# M16_EX.net
KiCad netlist of a schematic drawn in Altium Designer
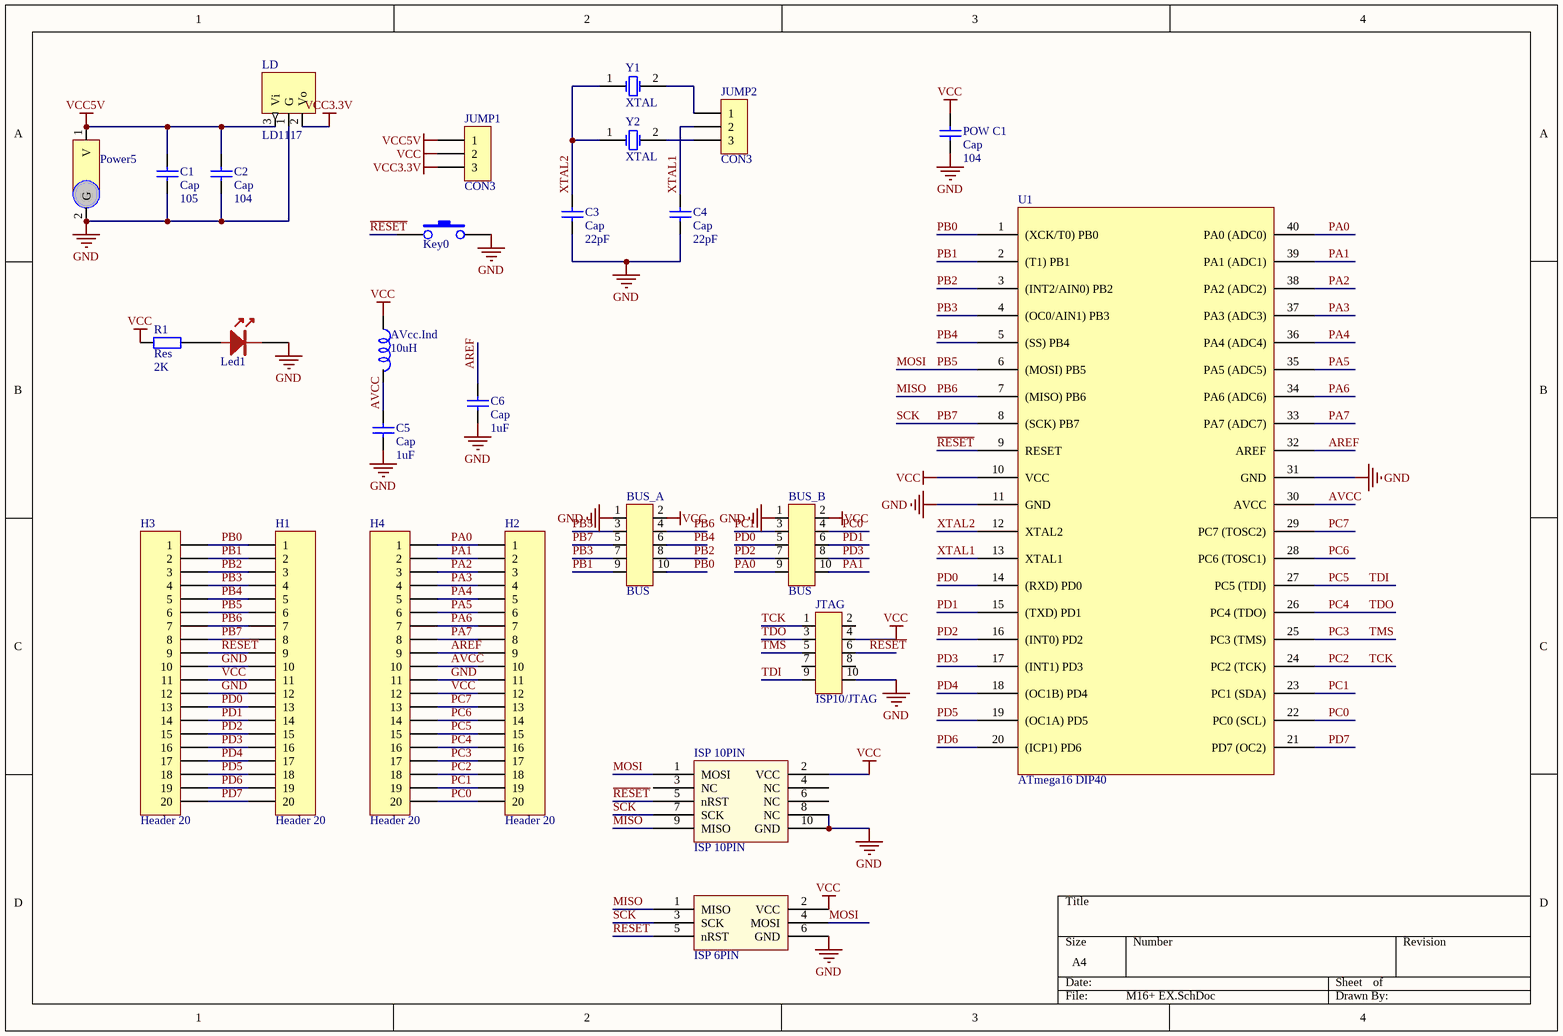
[diagram p0: M16+ EX.SchDoc]

(export (version "E")
  (design (tool "Eeschema 10.0.6"))
  (components
    (comp (ref "AVcc.Ind") (value "10uH") (footprint "RES") (libsource (lib "zz") (part "IND")))
    (comp (ref "BUS_A")
      (value "BUS")
      (footprint "ISP_10")
      (description "ISP_10")
      (libsource (lib "zz") (part "ISP_10"))
    )
    (comp (ref "BUS_B")
      (value "BUS")
      (footprint "ISP_10")
      (description "ISP_10")
      (libsource (lib "zz") (part "ISP_10"))
    )
    (comp (ref "C1")
      (value "Cap")
      (footprint "0805")
      (description "Capacitor")
      (fields (field (name "ALTIUM_VALUE") "105") (field (name "PUBLISHER") "Altium Limited"))
      (libsource (lib "Miscellaneous Devices") (part "Cap"))
    )
    (comp (ref "C2")
      (value "Cap")
      (footprint "0805")
      (description "Capacitor")
      (fields (field (name "ALTIUM_VALUE") "104") (field (name "PUBLISHER") "Altium Limited"))
      (libsource (lib "Miscellaneous Devices") (part "Cap"))
    )
    (comp (ref "C3")
      (value "Cap")
      (footprint "0603")
      (description "Capacitor")
      (fields (field (name "ALTIUM_VALUE") "22pF") (field (name "PUBLISHER") "Altium Limited"))
      (libsource (lib "Miscellaneous Devices") (part "Cap"))
    )
    (comp (ref "C4")
      (value "Cap")
      (footprint "0603")
      (description "Capacitor")
      (fields (field (name "ALTIUM_VALUE") "22pF") (field (name "PUBLISHER") "Altium Limited"))
      (libsource (lib "Miscellaneous Devices") (part "Cap"))
    )
    (comp (ref "C5")
      (value "Cap")
      (footprint "0805")
      (description "Capacitor")
      (fields (field (name "ALTIUM_VALUE") "1uF") (field (name "PUBLISHER") "Altium Limited"))
      (libsource (lib "Miscellaneous Devices") (part "Cap"))
    )
    (comp (ref "C6")
      (value "Cap")
      (footprint "0805")
      (description "Capacitor")
      (fields (field (name "ALTIUM_VALUE") "1uF") (field (name "PUBLISHER") "Altium Limited"))
      (libsource (lib "Miscellaneous Devices") (part "Cap"))
    )
    (comp (ref "H1")
      (value "Header 20")
      (footprint "SIP20")
      (description "Header, 20-Pin")
      (fields (field (name "PUBLISHER") "Altium Limited"))
      (libsource (lib "zz") (part "Header 20"))
    )
    (comp (ref "H2")
      (value "Header 20")
      (footprint "SIP20")
      (description "Header, 20-Pin")
      (fields (field (name "PUBLISHER") "Altium Limited"))
      (libsource (lib "zz") (part "Header 20"))
    )
    (comp (ref "H3")
      (value "Header 20")
      (footprint "SIP20")
      (description "Header, 20-Pin")
      (fields (field (name "PUBLISHER") "Altium Limited"))
      (libsource (lib "") (part "Header 20_1"))
    )
    (comp (ref "H4")
      (value "Header 20")
      (footprint "SIP20")
      (description "Header, 20-Pin")
      (fields (field (name "PUBLISHER") "Altium Limited"))
      (libsource (lib "") (part "Header 20_1"))
    )
    (comp (ref "ISP 6PIN") (value "ISP 6PIN") (footprint "ISP_6") (libsource (lib "zz") (part "ISP 6PIN")))
    (comp (ref "ISP 10PIN")
      (value "ISP 10PIN")
      (footprint "ISP_10")
      (libsource (lib "zz") (part "ISP 10PIN"))
    )
    (comp (ref "JTAG")
      (value "ISP10/JTAG")
      (footprint "ISP_10")
      (description "ISP_10")
      (libsource (lib "zz") (part "ISP_10"))
    )
    (comp (ref "JUMP1")
      (value "CON3")
      (footprint "SIP3")
      (description "Connector")
      (libsource (lib "zz") (part "CON3"))
    )
    (comp (ref "JUMP2")
      (value "CON3")
      (footprint "SIP3")
      (description "Connector")
      (libsource (lib "zz") (part "CON3"))
    )
    (comp (ref "Key0") (value "PB2") (footprint "KEY") (libsource (lib "zz") (part "KEY")))
    (comp (ref "LD") (value "LD1117") (footprint "LD1117-3.3") (libsource (lib "zz") (part "LD1117")))
    (comp (ref "Led1") (value "Led1") (footprint "0805_LED") (libsource (lib "zz") (part "LED")))
    (comp (ref "POW C1")
      (value "Cap")
      (footprint "0805")
      (description "Capacitor")
      (fields (field (name "ALTIUM_VALUE") "104") (field (name "PUBLISHER") "Altium Limited"))
      (libsource (lib "Miscellaneous Devices") (part "Cap"))
    )
    (comp (ref "Power5")
      (value "5V")
      (footprint "PWR_5V")
      (description "Power5")
      (libsource (lib "zz") (part "Power5"))
    )
    (comp (ref "R1")
      (value "Res")
      (footprint "0603")
      (description "Resistor")
      (fields (field (name "ALTIUM_VALUE") "2K") (field (name "PUBLISHER") "Altium Limited"))
      (libsource (lib "Miscellaneous Devices") (part "Res2"))
    )
    (comp (ref "U1")
      (value "ATmega16 DIP40")
      (footprint "DIP40 3M")
      (libsource (lib "zz") (part "ATmega16 DIP40"))
    )
    (comp (ref "Y1")
      (value "XTAL")
      (footprint "CRYSTAL")
      (description "Crystal Oscillator")
      (fields (field (name "PUBLISHER") "Altium Limited"))
      (libsource (lib "zz") (part "XTAL"))
    )
    (comp (ref "Y2")
      (value "XTAL")
      (footprint "CRYSTAL2")
      (description "Crystal Oscillator")
      (fields (field (name "PUBLISHER") "Altium Limited"))
      (libsource (lib "zz") (part "XTAL"))
    )
  )
  (nets
    (net (code "1") (name "/AREF") (class "Default")
      (node (ref "C6") (pin "2") (pinfunction "2_2") (pintype "passive"))
      (node (ref "H2") (pin "9") (pinfunction "9_9") (pintype "passive"))
      (node (ref "H4") (pin "9") (pinfunction "9_9") (pintype "passive"))
      (node (ref "U1") (pin "32") (pinfunction "AREF_32") (pintype "passive"))
    )
    (net (code "2") (name "/AVCC") (class "Default")
      (node (ref "AVcc.Ind") (pin "2") (pinfunction "1_2") (pintype "passive"))
      (node (ref "C5") (pin "2") (pinfunction "2_2") (pintype "passive"))
      (node (ref "H2") (pin "10") (pinfunction "10_10") (pintype "passive"))
      (node (ref "H4") (pin "10") (pinfunction "10_10") (pintype "passive"))
      (node (ref "U1") (pin "30") (pinfunction "AVCC_30") (pintype "passive"))
    )
    (net (code "3") (name "/MISO") (class "Default")
      (node (ref "BUS_A") (pin "4") (pintype "passive"))
      (node (ref "H1") (pin "7") (pinfunction "7_7") (pintype "passive"))
      (node (ref "H3") (pin "7") (pinfunction "7_7") (pintype "passive"))
      (node (ref "ISP 10PIN") (pin "9") (pinfunction "MISO_9") (pintype "passive"))
      (node (ref "ISP 6PIN") (pin "1") (pinfunction "MISO_1") (pintype "passive"))
      (node (ref "U1") (pin "7") (pinfunction "(MISO)_PB6_7") (pintype "passive"))
    )
    (net (code "4") (name "/MOSI") (class "Default")
      (node (ref "BUS_A") (pin "3") (pintype "passive"))
      (node (ref "H1") (pin "6") (pinfunction "6_6") (pintype "passive"))
      (node (ref "H3") (pin "6") (pinfunction "6_6") (pintype "passive"))
      (node (ref "ISP 10PIN") (pin "1") (pinfunction "MOSI_1") (pintype "passive"))
      (node (ref "ISP 6PIN") (pin "4") (pinfunction "MOSI_4") (pintype "passive"))
      (node (ref "U1") (pin "6") (pinfunction "(MOSI)_PB5_6") (pintype "passive"))
    )
    (net (code "5") (name "/PA0") (class "Default")
      (node (ref "BUS_B") (pin "9") (pintype "passive"))
      (node (ref "H2") (pin "1") (pinfunction "1_1") (pintype "passive"))
      (node (ref "H4") (pin "1") (pinfunction "1_1") (pintype "passive"))
      (node (ref "U1") (pin "40") (pinfunction "PA0_(ADC0)_40") (pintype "passive"))
    )
    (net (code "6") (name "/PA1") (class "Default")
      (node (ref "BUS_B") (pin "10") (pintype "passive"))
      (node (ref "H2") (pin "2") (pinfunction "2_2") (pintype "passive"))
      (node (ref "H4") (pin "2") (pinfunction "2_2") (pintype "passive"))
      (node (ref "U1") (pin "39") (pinfunction "PA1_(ADC1)_39") (pintype "passive"))
    )
    (net (code "7") (name "/PA2") (class "Default")
      (node (ref "H2") (pin "3") (pinfunction "3_3") (pintype "passive"))
      (node (ref "H4") (pin "3") (pinfunction "3_3") (pintype "passive"))
      (node (ref "U1") (pin "38") (pinfunction "PA2_(ADC2)_38") (pintype "passive"))
    )
    (net (code "8") (name "/PA3") (class "Default")
      (node (ref "H2") (pin "4") (pinfunction "4_4") (pintype "passive"))
      (node (ref "H4") (pin "4") (pinfunction "4_4") (pintype "passive"))
      (node (ref "U1") (pin "37") (pinfunction "PA3_(ADC3)_37") (pintype "passive"))
    )
    (net (code "9") (name "/PA4") (class "Default")
      (node (ref "H2") (pin "5") (pinfunction "5_5") (pintype "passive"))
      (node (ref "H4") (pin "5") (pinfunction "5_5") (pintype "passive"))
      (node (ref "U1") (pin "36") (pinfunction "PA4_(ADC4)_36") (pintype "passive"))
    )
    (net (code "10") (name "/PA5") (class "Default")
      (node (ref "H2") (pin "6") (pinfunction "6_6") (pintype "passive"))
      (node (ref "H4") (pin "6") (pinfunction "6_6") (pintype "passive"))
      (node (ref "U1") (pin "35") (pinfunction "PA5_(ADC5)_35") (pintype "passive"))
    )
    (net (code "11") (name "/PA6") (class "Default")
      (node (ref "H2") (pin "7") (pinfunction "7_7") (pintype "passive"))
      (node (ref "H4") (pin "7") (pinfunction "7_7") (pintype "passive"))
      (node (ref "U1") (pin "34") (pinfunction "PA6_(ADC6)_34") (pintype "passive"))
    )
    (net (code "12") (name "/PA7") (class "Default")
      (node (ref "H2") (pin "8") (pinfunction "8_8") (pintype "passive"))
      (node (ref "H4") (pin "8") (pinfunction "8_8") (pintype "passive"))
      (node (ref "U1") (pin "33") (pinfunction "PA7_(ADC7)_33") (pintype "passive"))
    )
    (net (code "13") (name "/PB0") (class "Default")
      (node (ref "BUS_A") (pin "10") (pintype "passive"))
      (node (ref "H1") (pin "1") (pinfunction "1_1") (pintype "passive"))
      (node (ref "H3") (pin "1") (pinfunction "1_1") (pintype "passive"))
      (node (ref "U1") (pin "1") (pinfunction "(XCK/T0)_PB0_1") (pintype "passive"))
    )
    (net (code "14") (name "/PB1") (class "Default")
      (node (ref "BUS_A") (pin "9") (pintype "passive"))
      (node (ref "H1") (pin "2") (pinfunction "2_2") (pintype "passive"))
      (node (ref "H3") (pin "2") (pinfunction "2_2") (pintype "passive"))
      (node (ref "U1") (pin "2") (pinfunction "(T1)_PB1_2") (pintype "passive"))
    )
    (net (code "15") (name "/PB2") (class "Default")
      (node (ref "BUS_A") (pin "8") (pintype "passive"))
      (node (ref "H1") (pin "3") (pinfunction "3_3") (pintype "passive"))
      (node (ref "H3") (pin "3") (pinfunction "3_3") (pintype "passive"))
      (node (ref "U1") (pin "3") (pinfunction "(INT2/AIN0)_PB2_3") (pintype "passive"))
    )
    (net (code "16") (name "/PB3") (class "Default")
      (node (ref "BUS_A") (pin "7") (pintype "passive"))
      (node (ref "H1") (pin "4") (pinfunction "4_4") (pintype "passive"))
      (node (ref "H3") (pin "4") (pinfunction "4_4") (pintype "passive"))
      (node (ref "U1") (pin "4") (pinfunction "(OC0/AIN1)_PB3_4") (pintype "passive"))
    )
    (net (code "17") (name "/PB4") (class "Default")
      (node (ref "BUS_A") (pin "6") (pintype "passive"))
      (node (ref "H1") (pin "5") (pinfunction "5_5") (pintype "passive"))
      (node (ref "H3") (pin "5") (pinfunction "5_5") (pintype "passive"))
      (node (ref "U1") (pin "5") (pinfunction "(SS)_PB4_5") (pintype "passive"))
    )
    (net (code "18") (name "/PB7") (class "Default")
      (node (ref "BUS_A") (pin "5") (pintype "passive"))
      (node (ref "H1") (pin "8") (pinfunction "8_8") (pintype "passive"))
      (node (ref "H3") (pin "8") (pinfunction "8_8") (pintype "passive"))
      (node (ref "ISP 10PIN") (pin "7") (pinfunction "SCK_7") (pintype "passive"))
      (node (ref "ISP 6PIN") (pin "3") (pinfunction "SCK_3") (pintype "passive"))
      (node (ref "U1") (pin "8") (pinfunction "(SCK)_PB7_8") (pintype "passive"))
    )
    (net (code "19") (name "/PC0") (class "Default")
      (node (ref "BUS_B") (pin "4") (pintype "passive"))
      (node (ref "H2") (pin "20") (pinfunction "20_20") (pintype "passive"))
      (node (ref "H4") (pin "20") (pinfunction "20_20") (pintype "passive"))
      (node (ref "U1") (pin "22") (pinfunction "PC0_(SCL)_22") (pintype "passive"))
    )
    (net (code "20") (name "/PC1") (class "Default")
      (node (ref "BUS_B") (pin "3") (pintype "passive"))
      (node (ref "H2") (pin "19") (pinfunction "19_19") (pintype "passive"))
      (node (ref "H4") (pin "19") (pinfunction "19_19") (pintype "passive"))
      (node (ref "U1") (pin "23") (pinfunction "PC1_(SDA)_23") (pintype "passive"))
    )
    (net (code "21") (name "/PC2") (class "Default")
      (node (ref "H2") (pin "18") (pinfunction "18_18") (pintype "passive"))
      (node (ref "H4") (pin "18") (pinfunction "18_18") (pintype "passive"))
      (node (ref "JTAG") (pin "1") (pintype "passive"))
      (node (ref "U1") (pin "24") (pinfunction "PC2_(TCK)_24") (pintype "passive"))
    )
    (net (code "22") (name "/PC3") (class "Default")
      (node (ref "H2") (pin "17") (pinfunction "17_17") (pintype "passive"))
      (node (ref "H4") (pin "17") (pinfunction "17_17") (pintype "passive"))
      (node (ref "JTAG") (pin "5") (pintype "passive"))
      (node (ref "U1") (pin "25") (pinfunction "PC3_(TMS)_25") (pintype "passive"))
    )
    (net (code "23") (name "/PC4") (class "Default")
      (node (ref "H2") (pin "16") (pinfunction "16_16") (pintype "passive"))
      (node (ref "H4") (pin "16") (pinfunction "16_16") (pintype "passive"))
      (node (ref "JTAG") (pin "3") (pintype "passive"))
      (node (ref "U1") (pin "26") (pinfunction "PC4_(TDO)_26") (pintype "passive"))
    )
    (net (code "24") (name "/PC5") (class "Default")
      (node (ref "H2") (pin "15") (pinfunction "15_15") (pintype "passive"))
      (node (ref "H4") (pin "15") (pinfunction "15_15") (pintype "passive"))
      (node (ref "JTAG") (pin "9") (pintype "passive"))
      (node (ref "U1") (pin "27") (pinfunction "PC5_(TDI)_27") (pintype "passive"))
    )
    (net (code "25") (name "/PC6") (class "Default")
      (node (ref "H2") (pin "14") (pinfunction "14_14") (pintype "passive"))
      (node (ref "H4") (pin "14") (pinfunction "14_14") (pintype "passive"))
      (node (ref "U1") (pin "28") (pinfunction "PC6_(TOSC1)_28") (pintype "passive"))
    )
    (net (code "26") (name "/PC7") (class "Default")
      (node (ref "H2") (pin "13") (pinfunction "13_13") (pintype "passive"))
      (node (ref "H4") (pin "13") (pinfunction "13_13") (pintype "passive"))
      (node (ref "U1") (pin "29") (pinfunction "PC7_(TOSC2)_29") (pintype "passive"))
    )
    (net (code "27") (name "/PD0") (class "Default")
      (node (ref "BUS_B") (pin "5") (pintype "passive"))
      (node (ref "H1") (pin "13") (pinfunction "13_13") (pintype "passive"))
      (node (ref "H3") (pin "13") (pinfunction "13_13") (pintype "passive"))
      (node (ref "U1") (pin "14") (pinfunction "(RXD)_PD0_14") (pintype "passive"))
    )
    (net (code "28") (name "/PD1") (class "Default")
      (node (ref "BUS_B") (pin "6") (pintype "passive"))
      (node (ref "H1") (pin "14") (pinfunction "14_14") (pintype "passive"))
      (node (ref "H3") (pin "14") (pinfunction "14_14") (pintype "passive"))
      (node (ref "U1") (pin "15") (pinfunction "(TXD)_PD1_15") (pintype "passive"))
    )
    (net (code "29") (name "/PD2") (class "Default")
      (node (ref "BUS_B") (pin "7") (pintype "passive"))
      (node (ref "H1") (pin "15") (pinfunction "15_15") (pintype "passive"))
      (node (ref "H3") (pin "15") (pinfunction "15_15") (pintype "passive"))
      (node (ref "U1") (pin "16") (pinfunction "(INT0)_PD2_16") (pintype "passive"))
    )
    (net (code "30") (name "/PD3") (class "Default")
      (node (ref "BUS_B") (pin "8") (pintype "passive"))
      (node (ref "H1") (pin "16") (pinfunction "16_16") (pintype "passive"))
      (node (ref "H3") (pin "16") (pinfunction "16_16") (pintype "passive"))
      (node (ref "U1") (pin "17") (pinfunction "(INT1)_PD3_17") (pintype "passive"))
    )
    (net (code "31") (name "/PD4") (class "Default")
      (node (ref "H1") (pin "17") (pinfunction "17_17") (pintype "passive"))
      (node (ref "H3") (pin "17") (pinfunction "17_17") (pintype "passive"))
      (node (ref "U1") (pin "18") (pinfunction "(OC1B)_PD4_18") (pintype "passive"))
    )
    (net (code "32") (name "/PD5") (class "Default")
      (node (ref "H1") (pin "18") (pinfunction "18_18") (pintype "passive"))
      (node (ref "H3") (pin "18") (pinfunction "18_18") (pintype "passive"))
      (node (ref "U1") (pin "19") (pinfunction "(OC1A)_PD5_19") (pintype "passive"))
    )
    (net (code "33") (name "/PD6") (class "Default")
      (node (ref "H1") (pin "19") (pinfunction "19_19") (pintype "passive"))
      (node (ref "H3") (pin "19") (pinfunction "19_19") (pintype "passive"))
      (node (ref "U1") (pin "20") (pinfunction "(ICP1)_PD6_20") (pintype "passive"))
    )
    (net (code "34") (name "/PD7") (class "Default")
      (node (ref "H1") (pin "20") (pinfunction "20_20") (pintype "passive"))
      (node (ref "H3") (pin "20") (pinfunction "20_20") (pintype "passive"))
      (node (ref "U1") (pin "21") (pinfunction "PD7_(OC2)_21") (pintype "passive"))
    )
    (net (code "35") (name "/XTAL1") (class "Default")
      (node (ref "C4") (pin "2") (pinfunction "2_2") (pintype "passive"))
      (node (ref "JUMP2") (pin "2") (pinfunction "2_2") (pintype "passive"))
      (node (ref "U1") (pin "13") (pinfunction "XTAL1_13") (pintype "passive"))
    )
    (net (code "36") (name "/XTAL2") (class "Default")
      (node (ref "C3") (pin "2") (pinfunction "2_2") (pintype "passive"))
      (node (ref "U1") (pin "12") (pinfunction "XTAL2_12") (pintype "passive"))
      (node (ref "Y1") (pin "1") (pinfunction "OSC1_1") (pintype "passive"))
      (node (ref "Y2") (pin "1") (pinfunction "OSC1_1") (pintype "passive"))
    )
    (net (code "37") (name "/~{RESET}") (class "Default")
      (node (ref "H1") (pin "9") (pinfunction "9_9") (pintype "passive"))
      (node (ref "H3") (pin "9") (pinfunction "9_9") (pintype "passive"))
      (node (ref "ISP 10PIN") (pin "5") (pinfunction "nRST_5") (pintype "passive"))
      (node (ref "ISP 6PIN") (pin "5") (pinfunction "nRST_5") (pintype "passive"))
      (node (ref "JTAG") (pin "6") (pintype "passive"))
      (node (ref "Key0") (pin "1") (pinfunction "1_1") (pintype "passive"))
      (node (ref "U1") (pin "9") (pinfunction "RESET_9") (pintype "passive"))
    )
    (net (code "38") (name "GND") (class "Default")
      (node (ref "BUS_A") (pin "1") (pintype "passive"))
      (node (ref "BUS_B") (pin "1") (pintype "passive"))
      (node (ref "C1") (pin "1") (pinfunction "1_1") (pintype "passive"))
      (node (ref "C2") (pin "1") (pinfunction "1_1") (pintype "passive"))
      (node (ref "C3") (pin "1") (pinfunction "1_1") (pintype "passive"))
      (node (ref "C4") (pin "1") (pinfunction "1_1") (pintype "passive"))
      (node (ref "C5") (pin "1") (pinfunction "1_1") (pintype "passive"))
      (node (ref "C6") (pin "1") (pinfunction "1_1") (pintype "passive"))
      (node (ref "H1") (pin "10") (pinfunction "10_10") (pintype "passive"))
      (node (ref "H1") (pin "12") (pinfunction "12_12") (pintype "passive"))
      (node (ref "H2") (pin "11") (pinfunction "11_11") (pintype "passive"))
      (node (ref "H3") (pin "10") (pinfunction "10_10") (pintype "passive"))
      (node (ref "H3") (pin "12") (pinfunction "12_12") (pintype "passive"))
      (node (ref "H4") (pin "11") (pinfunction "11_11") (pintype "passive"))
      (node (ref "ISP 10PIN") (pin "10") (pinfunction "GND_10") (pintype "passive"))
      (node (ref "ISP 10PIN") (pin "8") (pinfunction "NC_8") (pintype "passive"))
      (node (ref "ISP 6PIN") (pin "6") (pinfunction "GND_6") (pintype "passive"))
      (node (ref "JTAG") (pin "10") (pintype "passive"))
      (node (ref "Key0") (pin "2") (pinfunction "2_2") (pintype "passive"))
      (node (ref "LD") (pin "1") (pinfunction "G_1") (pintype "passive"))
      (node (ref "Led1") (pin "2") (pinfunction "2_2") (pintype "passive"))
      (node (ref "POW C1") (pin "1") (pinfunction "1_1") (pintype "passive"))
      (node (ref "Power5") (pin "2") (pinfunction "G_2") (pintype "passive"))
      (node (ref "U1") (pin "11") (pinfunction "GND_11") (pintype "passive"))
      (node (ref "U1") (pin "31") (pinfunction "GND_31") (pintype "passive"))
    )
    (net (code "39") (name "Net-(Led1-Pad1)") (class "Default")
      (node (ref "Led1") (pin "1") (pinfunction "1_1") (pintype "passive"))
      (node (ref "R1") (pin "1") (pinfunction "1_1") (pintype "passive"))
    )
    (net (code "40") (name "Net-(Y1-OSC2)") (class "Default")
      (node (ref "JUMP2") (pin "1") (pinfunction "1_1") (pintype "passive"))
      (node (ref "Y1") (pin "2") (pinfunction "OSC2_2") (pintype "passive"))
    )
    (net (code "41") (name "Net-(Y2-OSC2)") (class "Default")
      (node (ref "JUMP2") (pin "3") (pinfunction "3_3") (pintype "passive"))
      (node (ref "Y2") (pin "2") (pinfunction "OSC2_2") (pintype "passive"))
    )
    (net (code "42") (name "VCC") (class "Default")
      (node (ref "AVcc.Ind") (pin "1") (pinfunction "0_1") (pintype "passive"))
      (node (ref "BUS_A") (pin "2") (pintype "passive"))
      (node (ref "BUS_B") (pin "2") (pintype "passive"))
      (node (ref "H1") (pin "11") (pinfunction "11_11") (pintype "passive"))
      (node (ref "H2") (pin "12") (pinfunction "12_12") (pintype "passive"))
      (node (ref "H3") (pin "11") (pinfunction "11_11") (pintype "passive"))
      (node (ref "H4") (pin "12") (pinfunction "12_12") (pintype "passive"))
      (node (ref "ISP 10PIN") (pin "2") (pinfunction "VCC_2") (pintype "passive"))
      (node (ref "ISP 6PIN") (pin "2") (pinfunction "VCC_2") (pintype "passive"))
      (node (ref "JTAG") (pin "4") (pintype "passive"))
      (node (ref "JUMP1") (pin "2") (pinfunction "2_2") (pintype "passive"))
      (node (ref "POW C1") (pin "2") (pinfunction "2_2") (pintype "passive"))
      (node (ref "R1") (pin "2") (pinfunction "2_2") (pintype "passive"))
      (node (ref "U1") (pin "10") (pinfunction "VCC_10") (pintype "passive"))
    )
    (net (code "43") (name "VCC3.3V") (class "Default")
      (node (ref "JUMP1") (pin "3") (pinfunction "3_3") (pintype "passive"))
      (node (ref "LD") (pin "2") (pinfunction "Vo_2") (pintype "passive"))
    )
    (net (code "44") (name "VCC5V") (class "Default")
      (node (ref "C1") (pin "2") (pinfunction "2_2") (pintype "passive"))
      (node (ref "C2") (pin "2") (pinfunction "2_2") (pintype "passive"))
      (node (ref "JUMP1") (pin "1") (pinfunction "1_1") (pintype "passive"))
      (node (ref "LD") (pin "3") (pinfunction "Vi_3") (pintype "output"))
      (node (ref "Power5") (pin "1") (pinfunction "V_1") (pintype "passive"))
    )
    (net (code "45") (name "unconnected-(ISP 10PIN-NC-Pad3)") (class "Default")
      (node (ref "ISP 10PIN") (pin "3") (pinfunction "NC_3") (pintype "passive"))
    )
    (net (code "46") (name "unconnected-(ISP 10PIN-NC-Pad4)") (class "Default")
      (node (ref "ISP 10PIN") (pin "4") (pinfunction "NC_4") (pintype "passive"))
    )
    (net (code "47") (name "unconnected-(ISP 10PIN-NC-Pad6)") (class "Default")
      (node (ref "ISP 10PIN") (pin "6") (pinfunction "NC_6") (pintype "passive"))
    )
    (net (code "48") (name "unconnected-(JTAG-Pad2)") (class "Default")
      (node (ref "JTAG") (pin "2") (pintype "passive"))
    )
    (net (code "49") (name "unconnected-(JTAG-Pad7)") (class "Default")
      (node (ref "JTAG") (pin "7") (pintype "passive"))
    )
    (net (code "50") (name "unconnected-(JTAG-Pad8)") (class "Default")
      (node (ref "JTAG") (pin "8") (pintype "passive"))
    )
  )
)
